# k1fm-pico-balloon.net
KiCad netlist of a schematic drawn in EAGLE
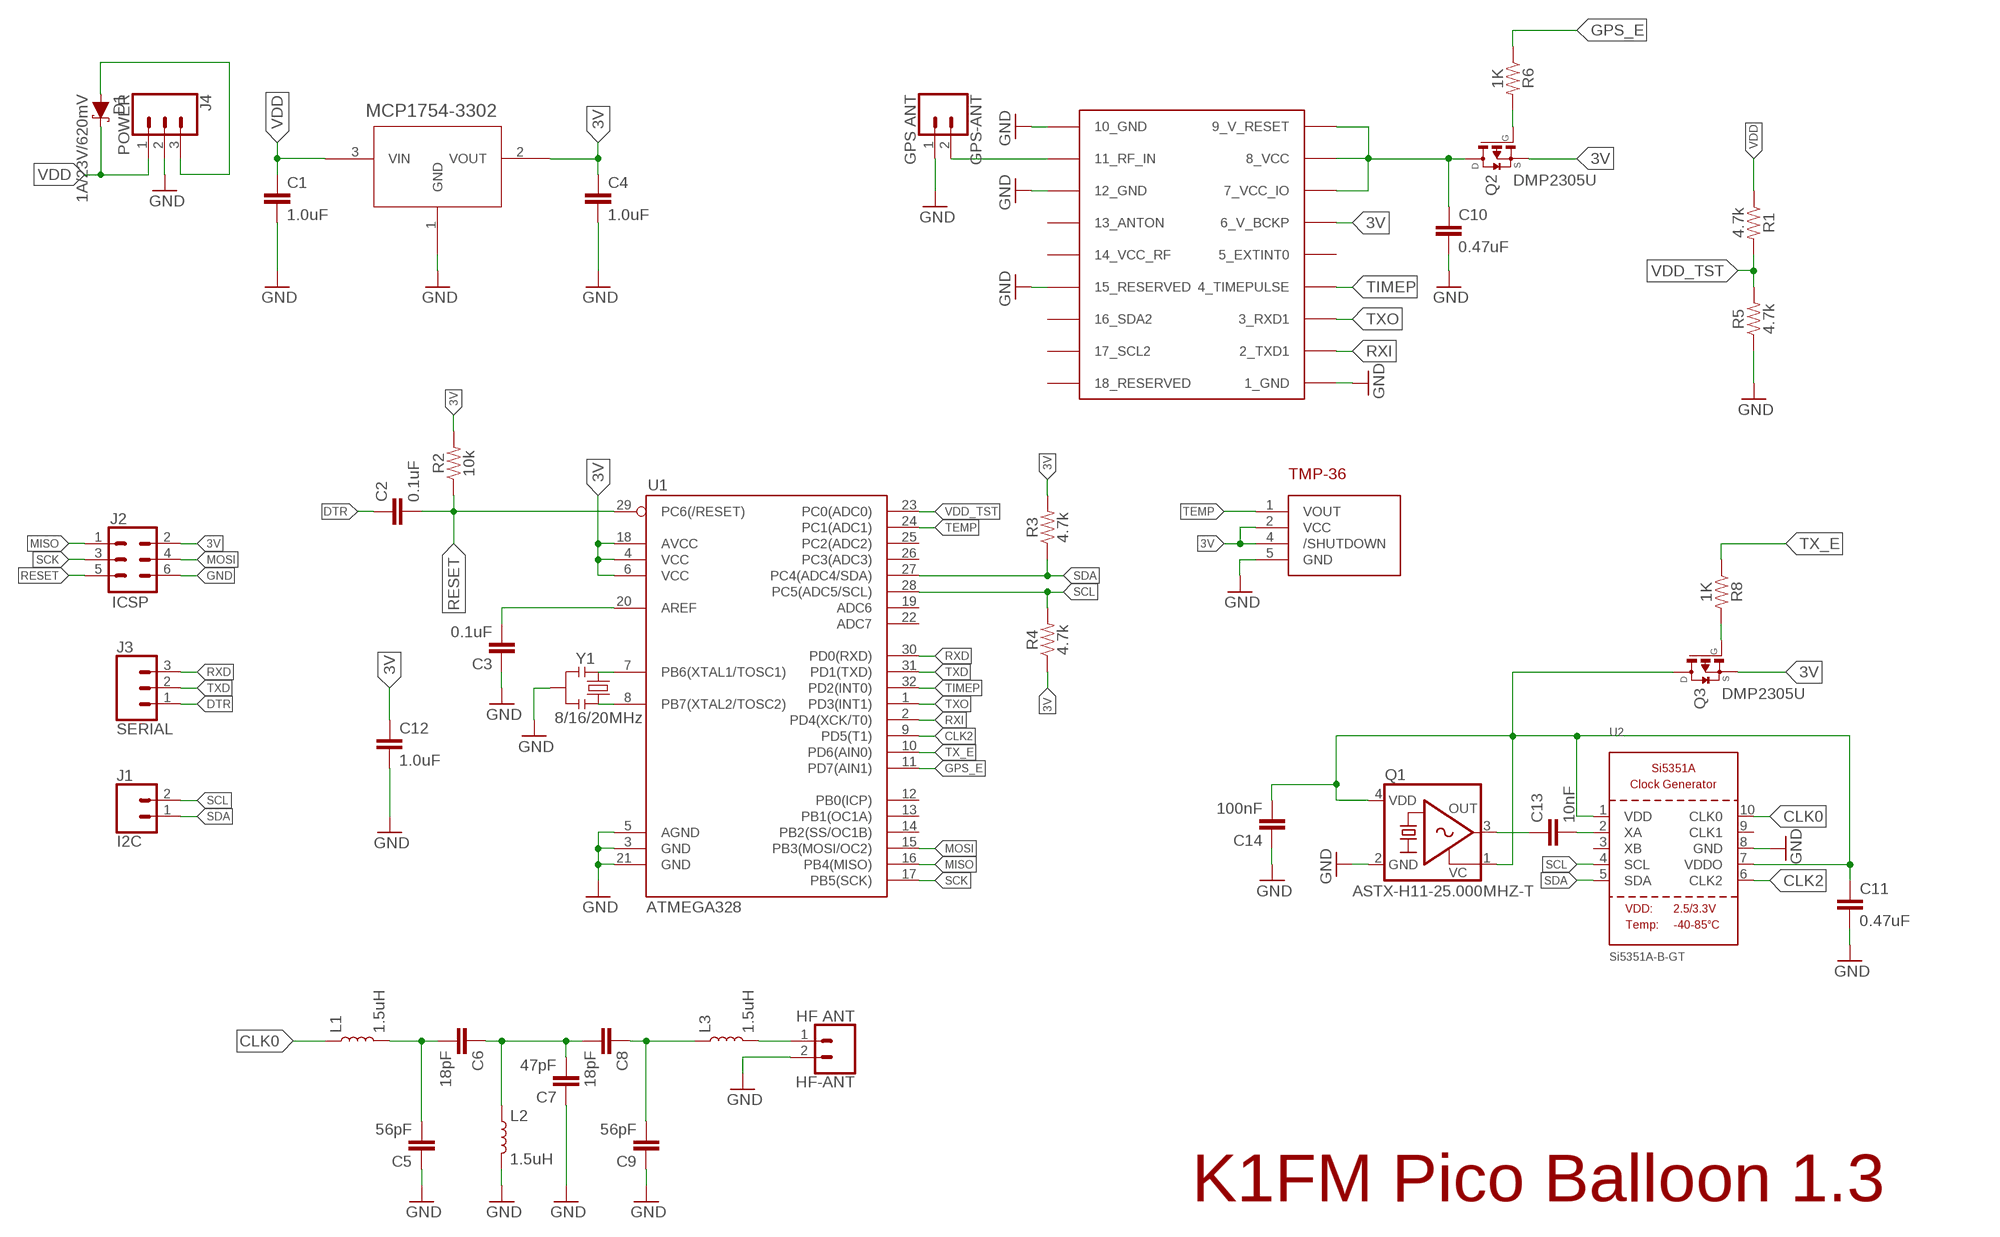
[diagram p0: schematic, sheet 1]

(export (version "E")
  (design (tool "Eeschema 10.0.6"))
  (components
    (comp (ref "C1")
      (value "1.0uF")
      (footprint "eagle-import:0603")
      (libsource (lib "eagle-import") (part "1.0UF-0603-16V-10%"))
    )
    (comp (ref "C2")
      (value "0.1uF")
      (footprint "eagle-import:0603")
      (libsource (lib "eagle-import") (part "0.1UF-0603-25V-5%"))
    )
    (comp (ref "C3")
      (value "0.1uF")
      (footprint "eagle-import:0603")
      (libsource (lib "eagle-import") (part "0.1UF-0603-25V-5%"))
    )
    (comp (ref "C4")
      (value "1.0uF")
      (footprint "eagle-import:0603")
      (libsource (lib "eagle-import") (part "1.0UF-0603-16V-10%"))
    )
    (comp (ref "C5")
      (value "56pF")
      (footprint "eagle-import:0603")
      (libsource (lib "eagle-import") (part "0.1UF-0603-25V-5%"))
    )
    (comp (ref "C6")
      (value "18pF")
      (footprint "eagle-import:0603")
      (libsource (lib "eagle-import") (part "0.1UF-0603-25V-5%"))
    )
    (comp (ref "C7")
      (value "47pF")
      (footprint "eagle-import:0603")
      (libsource (lib "eagle-import") (part "0.1UF-0603-25V-5%"))
    )
    (comp (ref "C8")
      (value "18pF")
      (footprint "eagle-import:0603")
      (libsource (lib "eagle-import") (part "0.1UF-0603-25V-5%"))
    )
    (comp (ref "C9")
      (value "56pF")
      (footprint "eagle-import:0603")
      (libsource (lib "eagle-import") (part "0.1UF-0603-25V-5%"))
    )
    (comp (ref "C10")
      (value "0.47uF")
      (footprint "eagle-import:0603")
      (libsource (lib "eagle-import") (part "0.1UF-0603-25V-5%"))
    )
    (comp (ref "C11")
      (value "0.47uF")
      (footprint "eagle-import:0603")
      (libsource (lib "eagle-import") (part "0.1UF-0603-25V-5%"))
    )
    (comp (ref "C12")
      (value "1.0uF")
      (footprint "eagle-import:0603")
      (libsource (lib "eagle-import") (part "1.0UF-0603-16V-10%"))
    )
    (comp (ref "C13")
      (value "10nF")
      (footprint "eagle-import:0603")
      (libsource (lib "eagle-import") (part "10NF-0603-50V-10%"))
    )
    (comp (ref "C14")
      (value "100nF")
      (footprint "eagle-import:0603")
      (libsource (lib "eagle-import") (part "10NF-0603-50V-10%"))
    )
    (comp (ref "D1")
      (value "1A/23V/620mV")
      (footprint "eagle-import:SOD-323")
      (libsource (lib "eagle-import") (part "DIODE-SCHOTTKY-BAT20J"))
    )
    (comp (ref "GPS-ANT")
      (value "GPS ANT")
      (footprint "eagle-import:1X02")
      (libsource (lib "eagle-import") (part "CONN_02"))
    )
    (comp (ref "GPS1")
      (value "UBLOX_MAX")
      (footprint "eagle-import:UBLOX_MAX")
      (libsource (lib "eagle-import") (part "UBLOX_MAX"))
    )
    (comp (ref "HF-ANT")
      (value "HF ANT")
      (footprint "eagle-import:1X02")
      (libsource (lib "eagle-import") (part "CONN_02"))
    )
    (comp (ref "J1")
      (value "I2C")
      (footprint "eagle-import:1X02")
      (libsource (lib "eagle-import") (part "CONN_02"))
    )
    (comp (ref "J2")
      (value "ICSP")
      (footprint "eagle-import:2X3")
      (libsource (lib "eagle-import") (part "CONN_03X2FEMALE"))
    )
    (comp (ref "J3")
      (value "SERIAL")
      (footprint "eagle-import:1X03")
      (libsource (lib "eagle-import") (part "CONN_03"))
    )
    (comp (ref "J4")
      (value "POWER")
      (footprint "eagle-import:1X03")
      (libsource (lib "eagle-import") (part "CONN_03"))
    )
    (comp (ref "L1")
      (value "1.5uH")
      (footprint "eagle-import:0603")
      (libsource (lib "eagle-import") (part "INDUCTOR-0603-33NH"))
    )
    (comp (ref "L2")
      (value "1.5uH")
      (footprint "eagle-import:0603")
      (libsource (lib "eagle-import") (part "INDUCTOR-0603-33NH"))
    )
    (comp (ref "L3")
      (value "1.5uH")
      (footprint "eagle-import:0603")
      (libsource (lib "eagle-import") (part "INDUCTOR-0603-33NH"))
    )
    (comp (ref "Q1")
      (value "ASTX-H11-25.000MHZ-T")
      (footprint "eagle-import:3.2X2.5_KXO-84")
      (libsource (lib "eagle-import") (part "KXO-VCXO-SINE-84"))
    )
    (comp (ref "Q2")
      (value "DMP2305U")
      (footprint "eagle-import:SOT23")
      (libsource (lib "eagle-import") (part "DMP2305U"))
    )
    (comp (ref "Q3")
      (value "DMP2305U")
      (footprint "eagle-import:SOT23")
      (libsource (lib "eagle-import") (part "DMP2305U"))
    )
    (comp (ref "R1")
      (value "4.7k")
      (footprint "eagle-import:0603")
      (libsource (lib "eagle-import") (part "10KOHM-0603-1/10W-1%"))
    )
    (comp (ref "R2")
      (value "10k")
      (footprint "eagle-import:0603")
      (libsource (lib "eagle-import") (part "10KOHM-0603-1/10W-1%"))
    )
    (comp (ref "R3")
      (value "4.7k")
      (footprint "eagle-import:0603")
      (libsource (lib "eagle-import") (part "4.7KOHM-0603-1/10W-1%"))
    )
    (comp (ref "R4")
      (value "4.7k")
      (footprint "eagle-import:0603")
      (libsource (lib "eagle-import") (part "4.7KOHM-0603-1/10W-1%"))
    )
    (comp (ref "R5")
      (value "4.7k")
      (footprint "eagle-import:0603")
      (libsource (lib "eagle-import") (part "10KOHM-0603-1/10W-1%"))
    )
    (comp (ref "R6")
      (value "1K")
      (footprint "eagle-import:0603")
      (libsource (lib "eagle-import") (part "10KOHM-0603-1/10W-1%"))
    )
    (comp (ref "R8")
      (value "1K")
      (footprint "eagle-import:0603")
      (libsource (lib "eagle-import") (part "10KOHM-0603-1/10W-1%"))
    )
    (comp (ref "U1")
      (value "ATMEGA328")
      (footprint "eagle-import:TQFP32-08")
      (libsource (lib "eagle-import") (part "ATMEGA168"))
    )
    (comp (ref "U2")
      (value "Si5351A-B-GT")
      (footprint "eagle-import:MSOP10")
      (libsource (lib "eagle-import") (part "SI5351A"))
    )
    (comp (ref "U3")
      (value "MCP1754X-XXXXX/C")
      (footprint "eagle-import:SOT-23A_MC")
      (libsource (lib "eagle-import") (part "MCP1754X-XXXXX/C"))
    )
    (comp (ref "U4")
      (value "TMP36")
      (footprint "eagle-import:SOT-23")
      (libsource (lib "eagle-import") (part "TMP36"))
    )
    (comp (ref "Y1")
      (value "8/16/20MHz")
      (footprint "eagle-import:RESONATOR-SMD-1_1")
      (libsource (lib "eagle-import") (part "RESONATOR1{colon}1"))
    )
  )
  (nets
    (net (code "1") (name "3V") (class "Default")
      (node (ref "C12") (pin "1") (pinfunction "1_1") (pintype "passive"))
      (node (ref "C4") (pin "1") (pinfunction "1_1") (pintype "passive"))
      (node (ref "GPS1") (pin "6_V_BCKP") (pinfunction "6_V_BCKP_6_V_BCKP") (pintype "bidirectional"))
      (node (ref "J2") (pin "2") (pinfunction "2_2") (pintype "bidirectional"))
      (node (ref "Q2") (pin "2") (pinfunction "S_2") (pintype "passive"))
      (node (ref "Q3") (pin "2") (pinfunction "S_2") (pintype "passive"))
      (node (ref "R2") (pin "2") (pinfunction "2_2") (pintype "passive"))
      (node (ref "R3") (pin "2") (pinfunction "2_2") (pintype "passive"))
      (node (ref "R4") (pin "1") (pinfunction "1_1") (pintype "passive"))
      (node (ref "U1") (pin "18") (pinfunction "AVCC_18") (pintype "bidirectional"))
      (node (ref "U1") (pin "4") (pinfunction "VCC_4") (pintype "bidirectional"))
      (node (ref "U1") (pin "6") (pinfunction "VCC_6") (pintype "bidirectional"))
      (node (ref "U3") (pin "2") (pinfunction "VOUT_2") (pintype "passive"))
      (node (ref "U4") (pin "2") (pinfunction "VCC_2") (pintype "bidirectional"))
      (node (ref "U4") (pin "4") (pinfunction "/SHUTDOWN_4") (pintype "bidirectional"))
    )
    (net (code "2") (name "CLK0") (class "Default")
      (node (ref "L1") (pin "1") (pinfunction "1_1") (pintype "passive"))
      (node (ref "U2") (pin "10") (pinfunction "CLK0_10") (pintype "output"))
    )
    (net (code "3") (name "CLK2") (class "Default")
      (node (ref "U1") (pin "9") (pinfunction "PD5(T1)_9") (pintype "bidirectional"))
      (node (ref "U2") (pin "6") (pinfunction "CLK2_6") (pintype "output"))
    )
    (net (code "4") (name "DTR") (class "Default")
      (node (ref "C2") (pin "1") (pinfunction "1_1") (pintype "passive"))
      (node (ref "J3") (pin "1") (pinfunction "1_1") (pintype "passive"))
    )
    (net (code "5") (name "GND") (class "Default")
      (node (ref "C1") (pin "2") (pinfunction "2_2") (pintype "passive"))
      (node (ref "C10") (pin "2") (pinfunction "2_2") (pintype "passive"))
      (node (ref "C11") (pin "2") (pinfunction "2_2") (pintype "passive"))
      (node (ref "C12") (pin "2") (pinfunction "2_2") (pintype "passive"))
      (node (ref "C14") (pin "1") (pinfunction "1_1") (pintype "passive"))
      (node (ref "C3") (pin "1") (pinfunction "1_1") (pintype "passive"))
      (node (ref "C4") (pin "2") (pinfunction "2_2") (pintype "passive"))
      (node (ref "C5") (pin "1") (pinfunction "1_1") (pintype "passive"))
      (node (ref "C7") (pin "1") (pinfunction "1_1") (pintype "passive"))
      (node (ref "C9") (pin "1") (pinfunction "1_1") (pintype "passive"))
      (node (ref "GPS-ANT") (pin "1") (pinfunction "1_1") (pintype "passive"))
      (node (ref "GPS1") (pin "10_GND") (pinfunction "10_GND_10_GND") (pintype "power_in"))
      (node (ref "GPS1") (pin "12_GND") (pinfunction "12_GND_12_GND") (pintype "power_in"))
      (node (ref "GPS1") (pin "15_RESERVED") (pinfunction "15_RESERVED_15_RESERVED") (pintype "bidirectional"))
      (node (ref "GPS1") (pin "1_GND") (pinfunction "1_GND_1_GND") (pintype "power_in"))
      (node (ref "HF-ANT") (pin "2") (pinfunction "2_2") (pintype "passive"))
      (node (ref "J2") (pin "6") (pinfunction "6_6") (pintype "bidirectional"))
      (node (ref "J4") (pin "2") (pinfunction "2_2") (pintype "passive"))
      (node (ref "L2") (pin "2") (pinfunction "2_2") (pintype "passive"))
      (node (ref "Q1") (pin "2") (pinfunction "GND_2") (pintype "power_in"))
      (node (ref "R5") (pin "1") (pinfunction "1_1") (pintype "passive"))
      (node (ref "U1") (pin "21") (pinfunction "GND_21") (pintype "bidirectional"))
      (node (ref "U1") (pin "3") (pinfunction "GND_3") (pintype "bidirectional"))
      (node (ref "U1") (pin "5") (pinfunction "AGND_5") (pintype "bidirectional"))
      (node (ref "U2") (pin "8") (pinfunction "GND_8") (pintype "power_in"))
      (node (ref "U3") (pin "1") (pinfunction "GND_1") (pintype "passive"))
      (node (ref "U4") (pin "5") (pinfunction "GND_5") (pintype "bidirectional"))
      (node (ref "Y1") (pin "2") (pinfunction "2_2") (pintype "passive"))
    )
    (net (code "6") (name "GPS_E") (class "Default")
      (node (ref "R6") (pin "1") (pinfunction "1_1") (pintype "passive"))
      (node (ref "U1") (pin "11") (pinfunction "PD7(AIN1)_11") (pintype "bidirectional"))
    )
    (net (code "7") (name "MISO") (class "Default")
      (node (ref "J2") (pin "1") (pinfunction "1_1") (pintype "bidirectional"))
      (node (ref "U1") (pin "16") (pinfunction "PB4(MISO)_16") (pintype "bidirectional"))
    )
    (net (code "8") (name "MOSI") (class "Default")
      (node (ref "J2") (pin "4") (pinfunction "4_4") (pintype "bidirectional"))
      (node (ref "U1") (pin "15") (pinfunction "PB3(MOSI/OC2)_15") (pintype "bidirectional"))
    )
    (net (code "9") (name "Net-(C5-Pad2)") (class "Default")
      (node (ref "C5") (pin "2") (pinfunction "2_2") (pintype "passive"))
      (node (ref "C6") (pin "2") (pinfunction "2_2") (pintype "passive"))
      (node (ref "L1") (pin "2") (pinfunction "2_2") (pintype "passive"))
    )
    (net (code "10") (name "Net-(C6-Pad1)") (class "Default")
      (node (ref "C6") (pin "1") (pinfunction "1_1") (pintype "passive"))
      (node (ref "C7") (pin "2") (pinfunction "2_2") (pintype "passive"))
      (node (ref "C8") (pin "2") (pinfunction "2_2") (pintype "passive"))
      (node (ref "L2") (pin "1") (pinfunction "1_1") (pintype "passive"))
    )
    (net (code "11") (name "Net-(C8-Pad1)") (class "Default")
      (node (ref "C8") (pin "1") (pinfunction "1_1") (pintype "passive"))
      (node (ref "C9") (pin "2") (pinfunction "2_2") (pintype "passive"))
      (node (ref "L3") (pin "1") (pinfunction "1_1") (pintype "passive"))
    )
    (net (code "12") (name "Net-(D1-PadA)") (class "Default")
      (node (ref "D1") (pin "A") (pinfunction "A_A") (pintype "passive"))
      (node (ref "J4") (pin "3") (pinfunction "3_3") (pintype "passive"))
    )
    (net (code "13") (name "Net-(GPS-ANT-Pad2)") (class "Default")
      (node (ref "GPS-ANT") (pin "2") (pinfunction "2_2") (pintype "passive"))
      (node (ref "GPS1") (pin "11_RF_IN") (pinfunction "11_RF_IN_11_RF_IN") (pintype "bidirectional"))
    )
    (net (code "14") (name "Net-(HF-ANT-Pad1)") (class "Default")
      (node (ref "HF-ANT") (pin "1") (pinfunction "1_1") (pintype "passive"))
      (node (ref "L3") (pin "2") (pinfunction "2_2") (pintype "passive"))
    )
    (net (code "15") (name "Net-(Q1-OUT)") (class "Default")
      (node (ref "C13") (pin "1") (pinfunction "1_1") (pintype "passive"))
      (node (ref "Q1") (pin "3") (pinfunction "OUT_3") (pintype "output"))
    )
    (net (code "16") (name "Net-(Q1-VC)") (class "Default")
      (node (ref "C11") (pin "1") (pinfunction "1_1") (pintype "passive"))
      (node (ref "C14") (pin "2") (pinfunction "2_2") (pintype "passive"))
      (node (ref "Q1") (pin "1") (pinfunction "VC_1") (pintype "input"))
      (node (ref "Q1") (pin "4") (pinfunction "VDD_4") (pintype "power_in"))
      (node (ref "Q3") (pin "3") (pinfunction "D_3") (pintype "passive"))
      (node (ref "U2") (pin "1") (pinfunction "VDD_1") (pintype "power_in"))
      (node (ref "U2") (pin "7") (pinfunction "VDDO_7") (pintype "power_in"))
    )
    (net (code "17") (name "Net-(Q2-D)") (class "Default")
      (node (ref "C10") (pin "1") (pinfunction "1_1") (pintype "passive"))
      (node (ref "GPS1") (pin "7_VCC_IO") (pinfunction "7_VCC_IO_7_VCC_IO") (pintype "power_in"))
      (node (ref "GPS1") (pin "8_VCC") (pinfunction "8_VCC_8_VCC") (pintype "power_in"))
      (node (ref "GPS1") (pin "9_V_RESET") (pinfunction "9_V_RESET_9_V_RESET") (pintype "power_in"))
      (node (ref "Q2") (pin "3") (pinfunction "D_3") (pintype "passive"))
    )
    (net (code "18") (name "Net-(Q2-G)") (class "Default")
      (node (ref "Q2") (pin "1") (pinfunction "G_1") (pintype "passive"))
      (node (ref "R6") (pin "2") (pinfunction "2_2") (pintype "passive"))
    )
    (net (code "19") (name "Net-(Q3-G)") (class "Default")
      (node (ref "Q3") (pin "1") (pinfunction "G_1") (pintype "passive"))
      (node (ref "R8") (pin "2") (pinfunction "2_2") (pintype "passive"))
    )
    (net (code "20") (name "Net-(U1-AREF)") (class "Default")
      (node (ref "C3") (pin "2") (pinfunction "2_2") (pintype "passive"))
      (node (ref "U1") (pin "20") (pinfunction "AREF_20") (pintype "bidirectional"))
    )
    (net (code "21") (name "Net-(U1-PB6(XTAL1{slash}TOSC1))") (class "Default")
      (node (ref "U1") (pin "7") (pinfunction "PB6(XTAL1/TOSC1)_7") (pintype "bidirectional"))
      (node (ref "Y1") (pin "1") (pinfunction "1_1") (pintype "passive"))
    )
    (net (code "22") (name "Net-(U1-PB7(XTAL2{slash}TOSC2))") (class "Default")
      (node (ref "U1") (pin "8") (pinfunction "PB7(XTAL2/TOSC2)_8") (pintype "bidirectional"))
      (node (ref "Y1") (pin "3") (pinfunction "3_3") (pintype "passive"))
    )
    (net (code "23") (name "Net-(U2-XA)") (class "Default")
      (node (ref "C13") (pin "2") (pinfunction "2_2") (pintype "passive"))
      (node (ref "U2") (pin "2") (pinfunction "XA_2") (pintype "input"))
    )
    (net (code "24") (name "RESET") (class "Default")
      (node (ref "C2") (pin "2") (pinfunction "2_2") (pintype "passive"))
      (node (ref "J2") (pin "5") (pinfunction "5_5") (pintype "bidirectional"))
      (node (ref "R2") (pin "1") (pinfunction "1_1") (pintype "passive"))
      (node (ref "U1") (pin "29") (pinfunction "PC6(/RESET)_29") (pintype "bidirectional"))
    )
    (net (code "25") (name "RXD") (class "Default")
      (node (ref "J3") (pin "3") (pinfunction "3_3") (pintype "passive"))
      (node (ref "U1") (pin "30") (pinfunction "PD0(RXD)_30") (pintype "bidirectional"))
    )
    (net (code "26") (name "RXI") (class "Default")
      (node (ref "GPS1") (pin "2_TXD1") (pinfunction "2_TXD1_2_TXD1") (pintype "bidirectional"))
      (node (ref "U1") (pin "2") (pinfunction "PD4(XCK/T0)_2") (pintype "bidirectional"))
    )
    (net (code "27") (name "SCK") (class "Default")
      (node (ref "J2") (pin "3") (pinfunction "3_3") (pintype "bidirectional"))
      (node (ref "U1") (pin "17") (pinfunction "PB5(SCK)_17") (pintype "bidirectional"))
    )
    (net (code "28") (name "SCL") (class "Default")
      (node (ref "J1") (pin "2") (pinfunction "2_2") (pintype "passive"))
      (node (ref "R4") (pin "2") (pinfunction "2_2") (pintype "passive"))
      (node (ref "U1") (pin "28") (pinfunction "PC5(ADC5/SCL)_28") (pintype "bidirectional"))
      (node (ref "U2") (pin "4") (pinfunction "SCL_4") (pintype "input"))
    )
    (net (code "29") (name "SDA") (class "Default")
      (node (ref "J1") (pin "1") (pinfunction "1_1") (pintype "passive"))
      (node (ref "R3") (pin "1") (pinfunction "1_1") (pintype "passive"))
      (node (ref "U1") (pin "27") (pinfunction "PC4(ADC4/SDA)_27") (pintype "bidirectional"))
      (node (ref "U2") (pin "5") (pinfunction "SDA_5") (pintype "bidirectional"))
    )
    (net (code "30") (name "TEMP") (class "Default")
      (node (ref "U1") (pin "24") (pinfunction "PC1(ADC1)_24") (pintype "bidirectional"))
      (node (ref "U4") (pin "1") (pinfunction "VOUT_1") (pintype "bidirectional"))
    )
    (net (code "31") (name "TIMEP") (class "Default")
      (node (ref "GPS1") (pin "4_TIMEPULSE") (pinfunction "4_TIMEPULSE_4_TIMEPULSE") (pintype "bidirectional"))
      (node (ref "U1") (pin "32") (pinfunction "PD2(INT0)_32") (pintype "bidirectional"))
    )
    (net (code "32") (name "TXD") (class "Default")
      (node (ref "J3") (pin "2") (pinfunction "2_2") (pintype "passive"))
      (node (ref "U1") (pin "31") (pinfunction "PD1(TXD)_31") (pintype "bidirectional"))
    )
    (net (code "33") (name "TXO") (class "Default")
      (node (ref "GPS1") (pin "3_RXD1") (pinfunction "3_RXD1_3_RXD1") (pintype "bidirectional"))
      (node (ref "U1") (pin "1") (pinfunction "PD3(INT1)_1") (pintype "bidirectional"))
    )
    (net (code "34") (name "TX_E") (class "Default")
      (node (ref "R8") (pin "1") (pinfunction "1_1") (pintype "passive"))
      (node (ref "U1") (pin "10") (pinfunction "PD6(AIN0)_10") (pintype "bidirectional"))
    )
    (net (code "35") (name "VDD") (class "Default")
      (node (ref "C1") (pin "1") (pinfunction "1_1") (pintype "passive"))
      (node (ref "D1") (pin "C") (pinfunction "C_C") (pintype "passive"))
      (node (ref "J4") (pin "1") (pinfunction "1_1") (pintype "passive"))
      (node (ref "R1") (pin "1") (pinfunction "1_1") (pintype "passive"))
      (node (ref "U3") (pin "3") (pinfunction "VIN_3") (pintype "passive"))
    )
    (net (code "36") (name "VDD_TST") (class "Default")
      (node (ref "R1") (pin "2") (pinfunction "2_2") (pintype "passive"))
      (node (ref "R5") (pin "2") (pinfunction "2_2") (pintype "passive"))
      (node (ref "U1") (pin "23") (pinfunction "PC0(ADC0)_23") (pintype "bidirectional"))
    )
    (net (code "37") (name "unconnected-(GPS1-Pad5_EXTINT0)") (class "Default")
      (node (ref "GPS1") (pin "5_EXTINT0") (pinfunction "5_EXTINT0_5_EXTINT0") (pintype "bidirectional"))
    )
    (net (code "38") (name "unconnected-(GPS1-Pad13_ANTON)") (class "Default")
      (node (ref "GPS1") (pin "13_ANTON") (pinfunction "13_ANTON_13_ANTON") (pintype "bidirectional"))
    )
    (net (code "39") (name "unconnected-(GPS1-Pad14_VCC_RF)") (class "Default")
      (node (ref "GPS1") (pin "14_VCC_RF") (pinfunction "14_VCC_RF_14_VCC_RF") (pintype "bidirectional"))
    )
    (net (code "40") (name "unconnected-(GPS1-Pad16_SDA2)") (class "Default")
      (node (ref "GPS1") (pin "16_SDA2") (pinfunction "16_SDA2_16_SDA2") (pintype "bidirectional"))
    )
    (net (code "41") (name "unconnected-(GPS1-Pad17_SCL2)") (class "Default")
      (node (ref "GPS1") (pin "17_SCL2") (pinfunction "17_SCL2_17_SCL2") (pintype "bidirectional"))
    )
    (net (code "42") (name "unconnected-(GPS1-Pad18_RESERVED)") (class "Default")
      (node (ref "GPS1") (pin "18_RESERVED") (pinfunction "18_RESERVED_18_RESERVED") (pintype "bidirectional"))
    )
    (net (code "43") (name "unconnected-(U1-ADC6-Pad19)") (class "Default")
      (node (ref "U1") (pin "19") (pinfunction "ADC6_19") (pintype "bidirectional"))
    )
    (net (code "44") (name "unconnected-(U1-ADC7-Pad22)") (class "Default")
      (node (ref "U1") (pin "22") (pinfunction "ADC7_22") (pintype "bidirectional"))
    )
    (net (code "45") (name "unconnected-(U1-PB0(ICP)-Pad12)") (class "Default")
      (node (ref "U1") (pin "12") (pinfunction "PB0(ICP)_12") (pintype "bidirectional"))
    )
    (net (code "46") (name "unconnected-(U1-PB1(OC1A)-Pad13)") (class "Default")
      (node (ref "U1") (pin "13") (pinfunction "PB1(OC1A)_13") (pintype "bidirectional"))
    )
    (net (code "47") (name "unconnected-(U1-PB2(SS{slash}OC1B)-Pad14)") (class "Default")
      (node (ref "U1") (pin "14") (pinfunction "PB2(SS/OC1B)_14") (pintype "bidirectional"))
    )
    (net (code "48") (name "unconnected-(U1-PC2(ADC2)-Pad25)") (class "Default")
      (node (ref "U1") (pin "25") (pinfunction "PC2(ADC2)_25") (pintype "bidirectional"))
    )
    (net (code "49") (name "unconnected-(U1-PC3(ADC3)-Pad26)") (class "Default")
      (node (ref "U1") (pin "26") (pinfunction "PC3(ADC3)_26") (pintype "bidirectional"))
    )
    (net (code "50") (name "unconnected-(U2-CLK1-Pad9)") (class "Default")
      (node (ref "U2") (pin "9") (pinfunction "CLK1_9") (pintype "output"))
    )
    (net (code "51") (name "unconnected-(U2-XB-Pad3)") (class "Default")
      (node (ref "U2") (pin "3") (pinfunction "XB_3") (pintype "input"))
    )
  )
)
